# Mechanic.net
KiCad netlist of a schematic drawn in Altium Designer
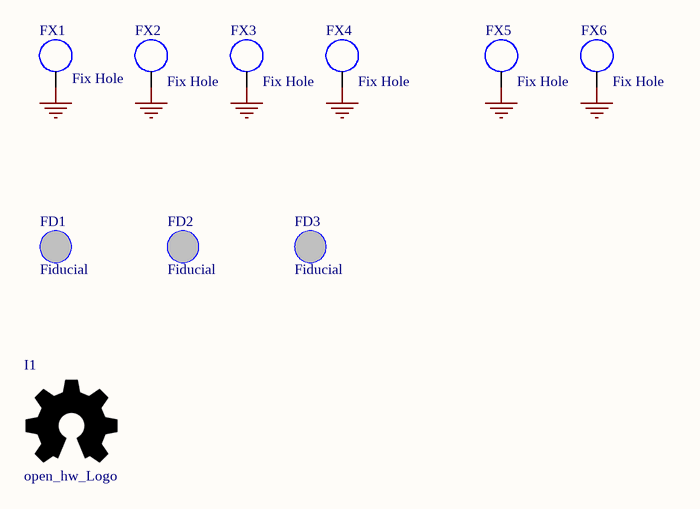
[diagram p0: Mechanic.SchDoc]

(export (version "E")
  (design (tool "Eeschema 10.0.6"))
  (components
    (comp (ref "FD1")
      (value "Fiducial")
      (footprint "Fiducial")
      (libsource (lib "Miscelanea") (part "Fiducial"))
    )
    (comp (ref "FD2")
      (value "Fiducial")
      (footprint "Fiducial")
      (libsource (lib "Miscelanea") (part "Fiducial"))
    )
    (comp (ref "FD3")
      (value "Fiducial")
      (footprint "Fiducial")
      (libsource (lib "Miscelanea") (part "Fiducial"))
    )
    (comp (ref "FX1")
      (value "Fix Hole")
      (footprint "Fix_Hole_3mm_5mmPad")
      (fields (field (name "PART NUMBER") "FX_3_5pad"))
      (libsource (lib "Miscelanea") (part "Fix Hole"))
    )
    (comp (ref "FX2")
      (value "Fix Hole")
      (footprint "Fix_Hole_3mm_5mmPad")
      (fields (field (name "PART NUMBER") "FX_3_5pad"))
      (libsource (lib "Miscelanea") (part "Fix Hole"))
    )
    (comp (ref "FX3")
      (value "Fix Hole")
      (footprint "Fix_Hole_3mm_5mmPad")
      (fields (field (name "PART NUMBER") "FX_3_5pad"))
      (libsource (lib "Miscelanea") (part "Fix Hole"))
    )
    (comp (ref "FX4")
      (value "Fix Hole")
      (footprint "Fix_Hole_3mm_5mmPad")
      (fields (field (name "PART NUMBER") "FX_3_5pad"))
      (libsource (lib "Miscelanea") (part "Fix Hole"))
    )
    (comp (ref "FX5")
      (value "Fix Hole")
      (footprint "Fix_Hole_3mm")
      (fields (field (name "PART NUMBER") "FX_3"))
      (libsource (lib "Miscelanea") (part "Fix Hole"))
    )
    (comp (ref "FX6")
      (value "Fix Hole")
      (footprint "Fix_Hole_3mm")
      (fields (field (name "PART NUMBER") "FX_3"))
      (libsource (lib "Miscelanea") (part "Fix Hole"))
    )
    (comp (ref "I1")
      (value "open_hw_Logo")
      (footprint "open_hw_Logo_small")
      (fields (field (name "PART NUMBER") "Open HW Logo Small"))
      (libsource (lib "Miscelanea") (part "open_hw_Logo"))
    )
  )
  (nets
    (net (code "1") (name "GND") (class "Default")
      (node (ref "FX1") (pin "1") (pinfunction "1_1") (pintype "passive"))
      (node (ref "FX2") (pin "1") (pinfunction "1_1") (pintype "passive"))
      (node (ref "FX3") (pin "1") (pinfunction "1_1") (pintype "passive"))
      (node (ref "FX4") (pin "1") (pinfunction "1_1") (pintype "passive"))
      (node (ref "FX5") (pin "1") (pinfunction "1_1") (pintype "passive"))
      (node (ref "FX6") (pin "1") (pinfunction "1_1") (pintype "passive"))
    )
  )
)
